# open-lux-C.net
KiCad netlist of a schematic drawn in EAGLE
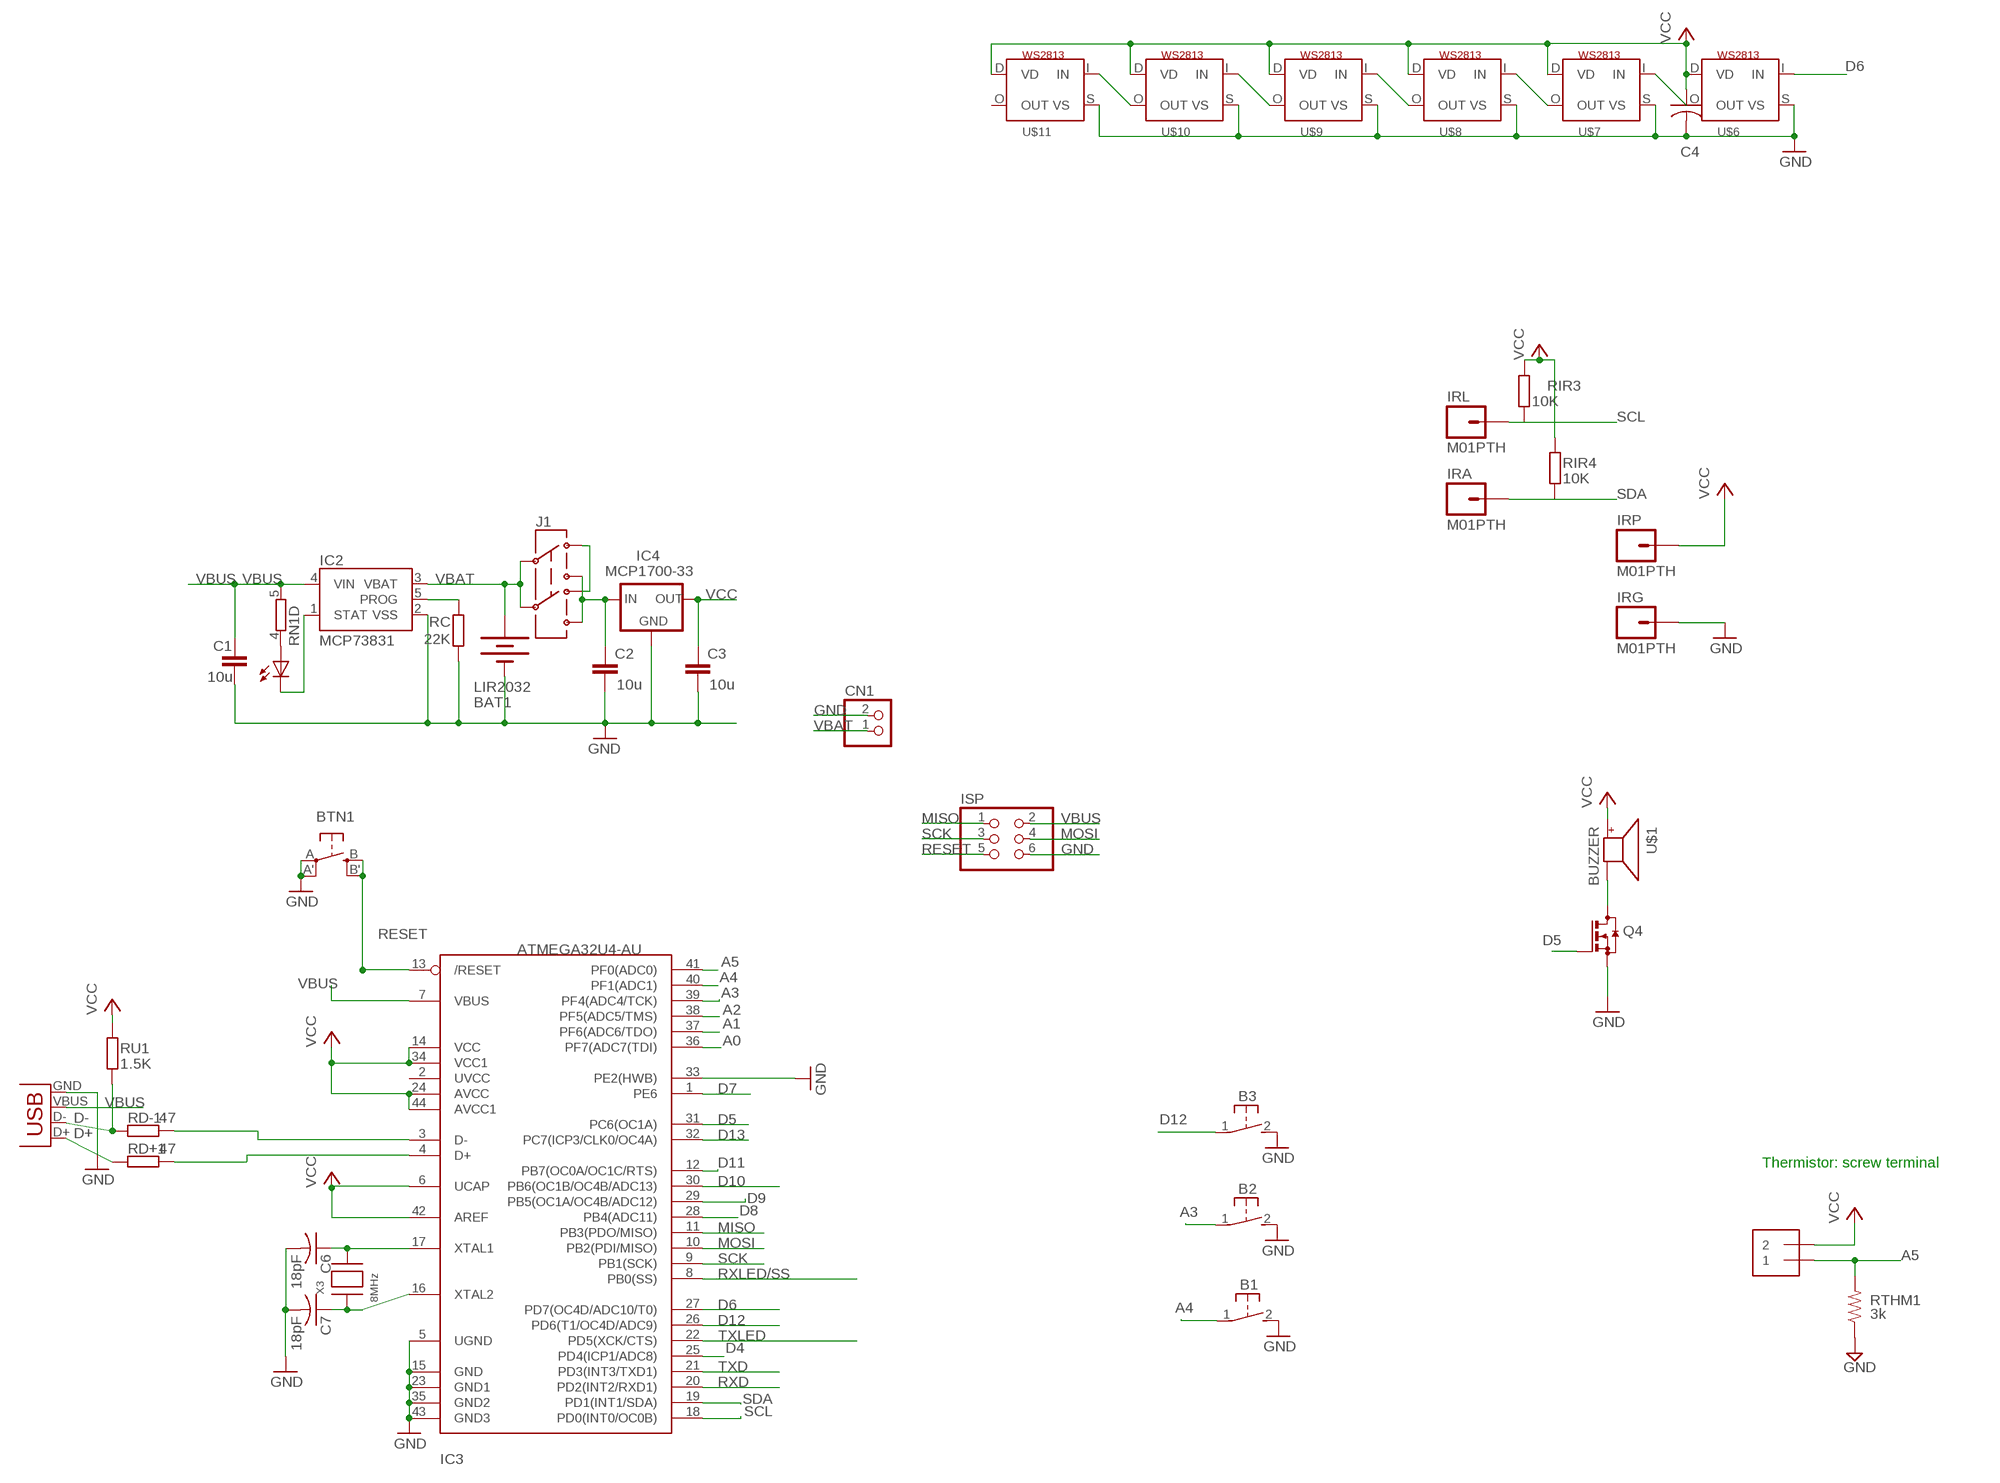
[diagram p0: schematic, sheet 1, part 1 of 2]
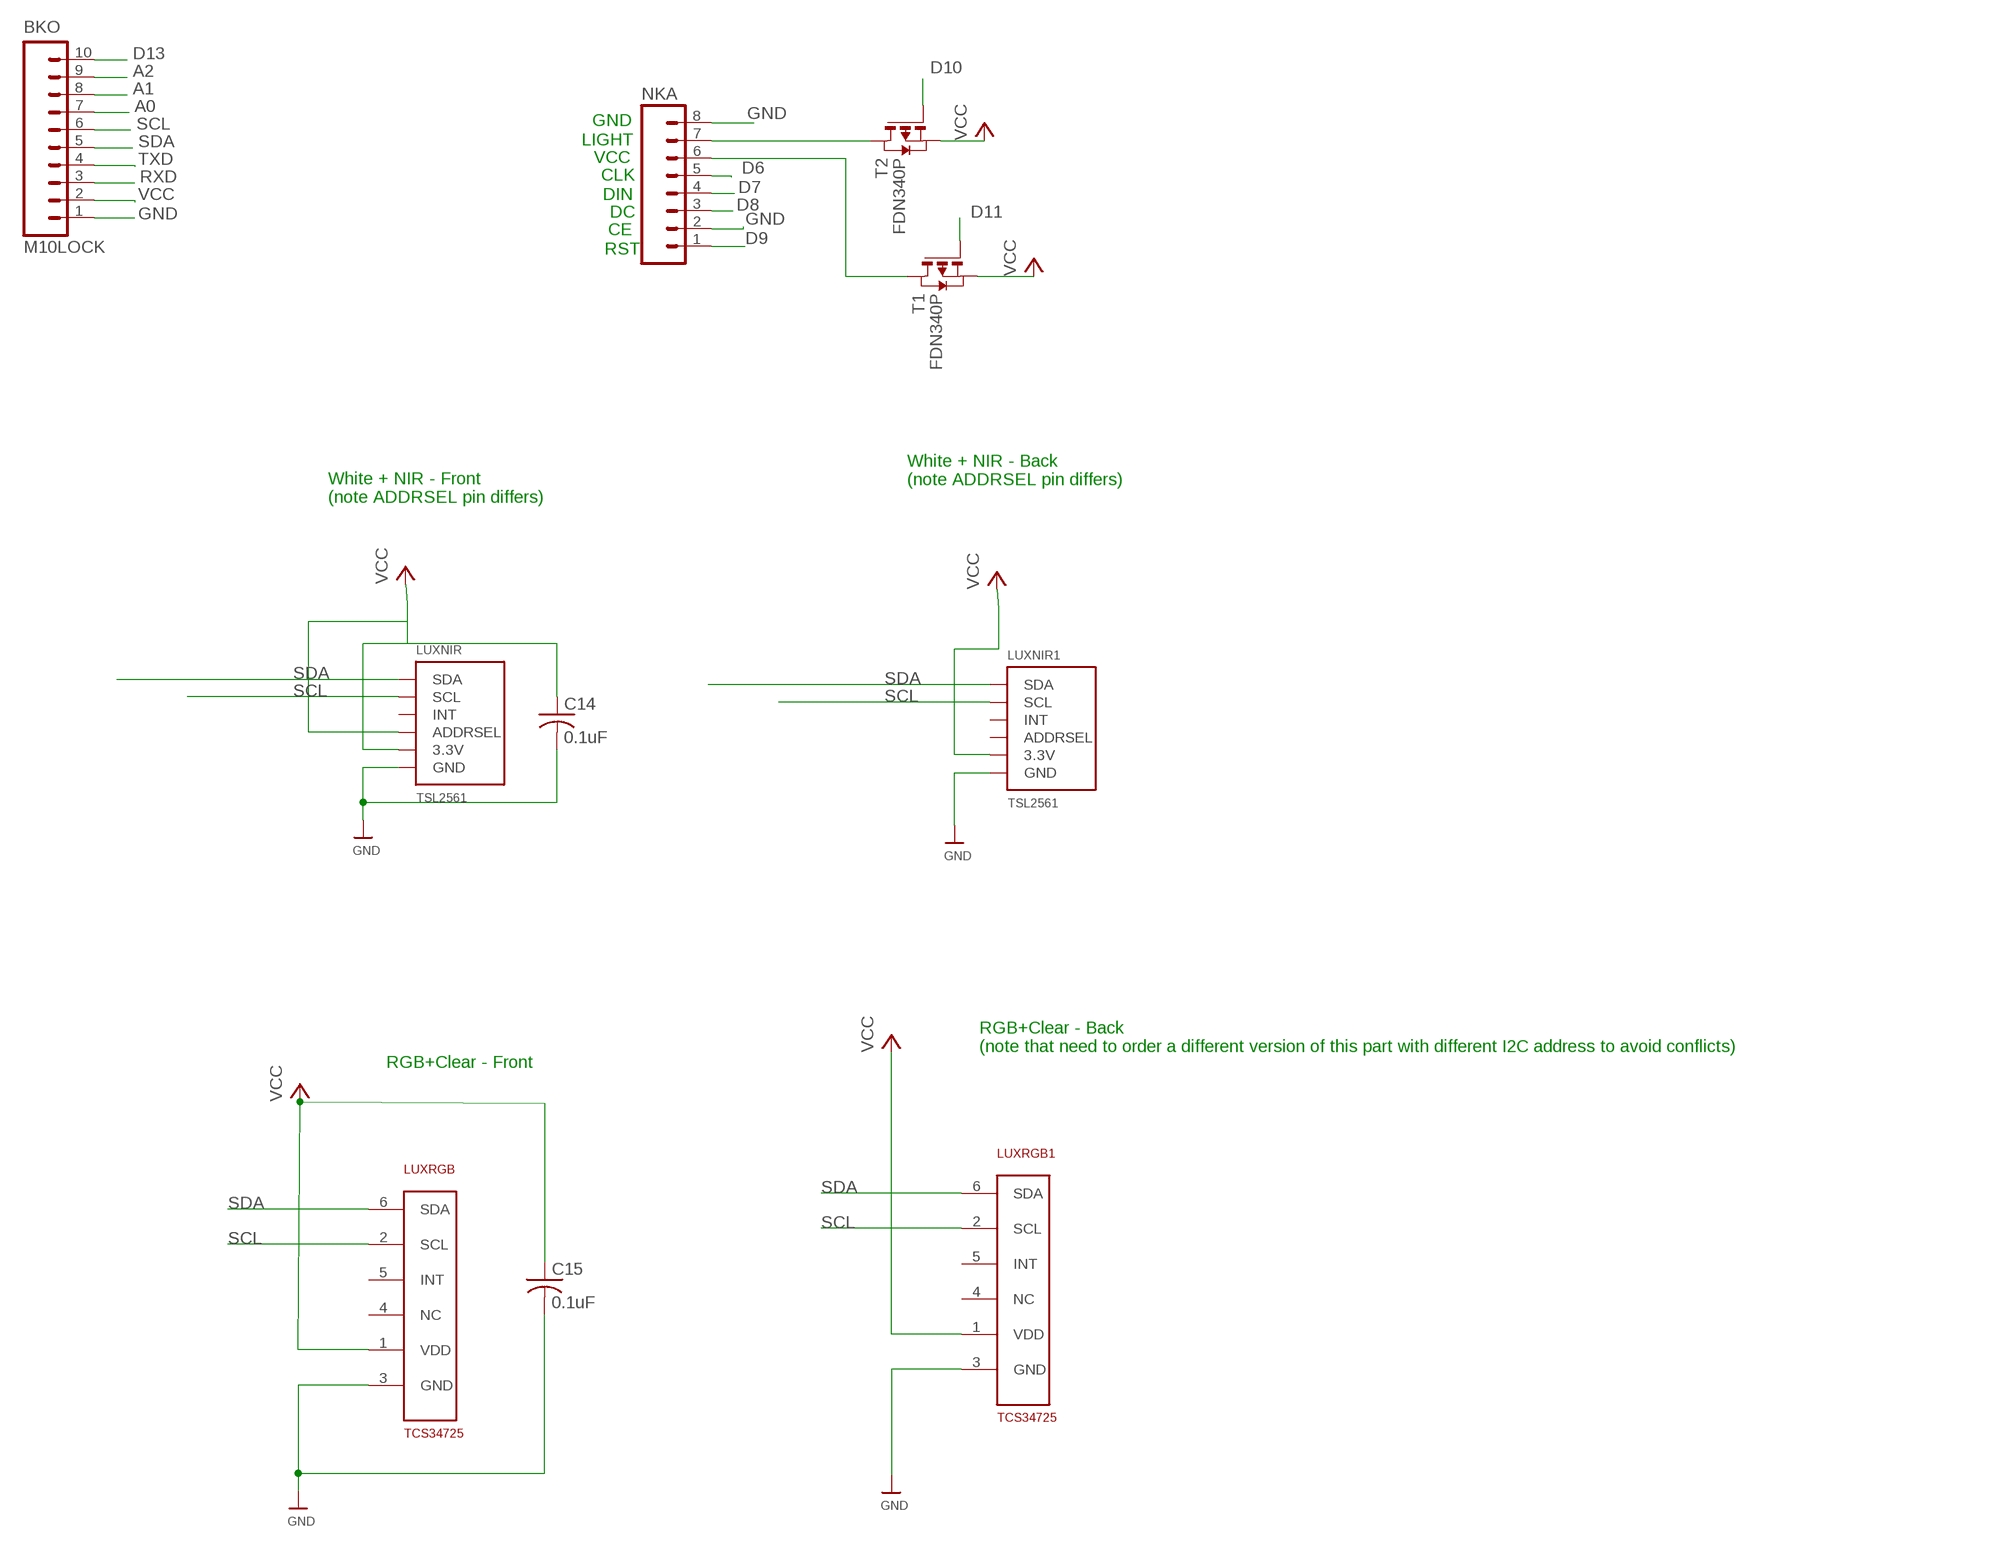
[diagram p1: schematic, sheet 1, part 2 of 2]

(export (version "E")
  (design (tool "Eeschema 10.0.6"))
  (components
    (comp (ref "B1")
      (value "31-XX")
      (footprint "eagle-import:B3F-31XX")
      (libsource (lib "eagle-import") (part "31-XX"))
    )
    (comp (ref "B2")
      (value "31-XX")
      (footprint "eagle-import:B3F-31XX")
      (libsource (lib "eagle-import") (part "31-XX"))
    )
    (comp (ref "B3")
      (value "31-XX")
      (footprint "eagle-import:B3F-31XX")
      (libsource (lib "eagle-import") (part "31-XX"))
    )
    (comp (ref "BAT1")
      (value "LIR2032")
      (footprint "eagle-import:BATTCOM_20MM_PTH_SMT")
      (libsource (lib "eagle-import") (part "BATTERYBATTCOM_20MM_PTH_SMT"))
    )
    (comp (ref "BKO")
      (value "M10LOCK")
      (footprint "eagle-import:1X10_LOCK")
      (libsource (lib "eagle-import") (part "M10LOCK"))
    )
    (comp (ref "BTN1")
      (value "EVQQ2")
      (footprint "eagle-import:EVQ-Q2")
      (libsource (lib "eagle-import") (part "EVQQ2"))
    )
    (comp (ref "C1")
      (value "10u")
      (footprint "eagle-import:C0805")
      (libsource (lib "eagle-import") (part "C-EUC0805"))
    )
    (comp (ref "C2")
      (value "10u")
      (footprint "eagle-import:C0805")
      (libsource (lib "eagle-import") (part "C-EUC0805"))
    )
    (comp (ref "C3")
      (value "10u")
      (footprint "eagle-import:C0805")
      (libsource (lib "eagle-import") (part "C-EUC0805"))
    )
    (comp (ref "C4")
      (value "C-USC0805K")
      (footprint "eagle-import:C0805K")
      (libsource (lib "eagle-import") (part "adafruit2013_C-USC0805K"))
    )
    (comp (ref "C6")
      (value "18pF")
      (footprint "eagle-import:C0805K")
      (libsource (lib "eagle-import") (part "C-USC0805K"))
    )
    (comp (ref "C7")
      (value "18pF")
      (footprint "eagle-import:C0805K")
      (libsource (lib "eagle-import") (part "C-USC0805K"))
    )
    (comp (ref "C14")
      (value "0.1uF")
      (footprint "eagle-import:C0805")
      (libsource (lib "eagle-import") (part "C-USC0805"))
    )
    (comp (ref "C15")
      (value "0.1uF")
      (footprint "eagle-import:C0805")
      (libsource (lib "eagle-import") (part "C-USC0805"))
    )
    (comp (ref "CHG")
      (value "0805")
      (footprint "eagle-import:CHIPLED_0805")
      (libsource (lib "eagle-import") (part "LEDCHIPLED_0805"))
    )
    (comp (ref "CN1")
      (value "JST_2PIN-SMT-RA")
      (footprint "eagle-import:JST-PH-2-SMT-RA")
      (libsource (lib "eagle-import") (part "JST_2PIN-SMT-RA"))
    )
    (comp (ref "IC2")
      (value "MCP73831")
      (footprint "eagle-import:SOT23-5")
      (libsource (lib "eagle-import") (part "MCP73831"))
    )
    (comp (ref "IC3")
      (value "ATMEGA32U4-AU")
      (footprint "eagle-import:TQFP44")
      (libsource (lib "eagle-import") (part "ATMEGA32U4-AU"))
    )
    (comp (ref "IC4")
      (value "MCP1700-33")
      (footprint "eagle-import:SOT23")
      (libsource (lib "eagle-import") (part "MCP1700SOT233"))
    )
    (comp (ref "IRA")
      (value "M01PTH")
      (footprint "eagle-import:1X01")
      (libsource (lib "eagle-import") (part "M01PTH"))
    )
    (comp (ref "IRG")
      (value "M01PTH")
      (footprint "eagle-import:1X01")
      (libsource (lib "eagle-import") (part "M01PTH"))
    )
    (comp (ref "IRL")
      (value "M01PTH")
      (footprint "eagle-import:1X01")
      (libsource (lib "eagle-import") (part "M01PTH"))
    )
    (comp (ref "IRP")
      (value "M01PTH")
      (footprint "eagle-import:1X01")
      (libsource (lib "eagle-import") (part "M01PTH"))
    )
    (comp (ref "ISP")
      (value "PINHD-2X3")
      (footprint "eagle-import:2X03")
      (libsource (lib "eagle-import") (part "PINHD-2X3"))
    )
    (comp (ref "J1")
      (value "AYZ0202")
      (footprint "eagle-import:AYZ0202")
      (libsource (lib "eagle-import") (part "AYZ0202"))
    )
    (comp (ref "LUXNIR")
      (value "TSL2561")
      (footprint "eagle-import:TSL2561_FN@1")
      (libsource (lib "eagle-import") (part "TSL2561"))
    )
    (comp (ref "LUXNIR1")
      (value "TSL2561")
      (footprint "eagle-import:TSL2561_FN@1")
      (libsource (lib "eagle-import") (part "TSL2561"))
    )
    (comp (ref "LUXRGB")
      (value "TCS34725")
      (footprint "eagle-import:DFN-6")
      (libsource (lib "eagle-import") (part "TCS34725"))
    )
    (comp (ref "LUXRGB1")
      (value "TCS34725")
      (footprint "eagle-import:DFN-6")
      (libsource (lib "eagle-import") (part "TCS34725"))
    )
    (comp (ref "NKA")
      (value "M08LOCK")
      (footprint "eagle-import:1X08_LOCK")
      (libsource (lib "eagle-import") (part "M08LOCK"))
    )
    (comp (ref "Q4")
      (value "BSS123")
      (footprint "eagle-import:SOT23")
      (libsource (lib "eagle-import") (part "BSS123"))
    )
    (comp (ref "RC")
      (value "22K")
      (footprint "eagle-import:R0805")
      (libsource (lib "eagle-import") (part "R-EU_R0805"))
    )
    (comp (ref "RD+1")
      (value "47")
      (footprint "eagle-import:R0805")
      (libsource (lib "eagle-import") (part "R-EU_R0805"))
    )
    (comp (ref "RD-1")
      (value "47")
      (footprint "eagle-import:R0805")
      (libsource (lib "eagle-import") (part "R-EU_R0805"))
    )
    (comp (ref "RIR3")
      (value "10K")
      (footprint "eagle-import:R0805")
      (libsource (lib "eagle-import") (part "R-EU_R0805"))
    )
    (comp (ref "RIR4")
      (value "10K")
      (footprint "eagle-import:R0805")
      (libsource (lib "eagle-import") (part "R-EU_R0805"))
    )
    (comp (ref "RN1")
      (value "4R-NEXB38V")
      (footprint "eagle-import:EXB38V")
      (libsource (lib "eagle-import") (part "4R-NEXB38V"))
    )
    (comp (ref "RTHM1")
      (value "3k")
      (footprint "eagle-import:R0805@1")
      (libsource (lib "eagle-import") (part "R-US_R0805"))
    )
    (comp (ref "RU1")
      (value "1.5K")
      (footprint "eagle-import:R0805")
      (libsource (lib "eagle-import") (part "R-EU_R0805"))
    )
    (comp (ref "T1")
      (value "FDN340P")
      (footprint "eagle-import:SOT-23")
      (libsource (lib "eagle-import") (part "PMOSSOT23"))
    )
    (comp (ref "T2")
      (value "FDN340P")
      (footprint "eagle-import:SOT-23")
      (libsource (lib "eagle-import") (part "PMOSSOT23"))
    )
    (comp (ref "THM1")
      (value "1X2-3.5MM")
      (footprint "eagle-import:1X2-3.5MM")
      (libsource (lib "eagle-import") (part "1X2-3.5MM"))
    )
    (comp (ref "U$1")
      (value "BUZZER")
      (footprint "eagle-import:SMT-8585-BUZZER")
      (libsource (lib "eagle-import") (part "BUZZER"))
    )
    (comp (ref "U$6")
      (value "WS2813")
      (footprint "eagle-import:RGBLED5050_4")
      (libsource (lib "eagle-import") (part "WS2813"))
    )
    (comp (ref "U$7")
      (value "WS2813")
      (footprint "eagle-import:RGBLED5050_4")
      (libsource (lib "eagle-import") (part "WS2813"))
    )
    (comp (ref "U$8")
      (value "WS2813")
      (footprint "eagle-import:RGBLED5050_4")
      (libsource (lib "eagle-import") (part "WS2813"))
    )
    (comp (ref "U$9")
      (value "WS2813")
      (footprint "eagle-import:RGBLED5050_4")
      (libsource (lib "eagle-import") (part "WS2813"))
    )
    (comp (ref "U$10")
      (value "WS2813")
      (footprint "eagle-import:RGBLED5050_4")
      (libsource (lib "eagle-import") (part "WS2813"))
    )
    (comp (ref "U$11")
      (value "WS2813")
      (footprint "eagle-import:RGBLED5050_4")
      (libsource (lib "eagle-import") (part "WS2813"))
    )
    (comp (ref "X2")
      (value "USBSMD")
      (footprint "eagle-import:USB-MINIB")
      (libsource (lib "eagle-import") (part "USBSMD"))
    )
    (comp (ref "X3")
      (value "8MHz")
      (footprint "eagle-import:NX5032")
      (libsource (lib "eagle-import") (part "XTALNX5032"))
    )
  )
  (nets
    (net (code "1") (name "/A0") (class "Default")
      (node (ref "BKO") (pin "7") (pinfunction "7_7") (pintype "passive"))
      (node (ref "IC3") (pin "36") (pinfunction "PF7(ADC7(TDI)_36") (pintype "bidirectional"))
    )
    (net (code "2") (name "/A1") (class "Default")
      (node (ref "BKO") (pin "8") (pinfunction "8_8") (pintype "passive"))
      (node (ref "IC3") (pin "37") (pinfunction "PF6(ADC6/TDO)_37") (pintype "bidirectional"))
    )
    (net (code "3") (name "/A2") (class "Default")
      (node (ref "BKO") (pin "9") (pinfunction "9_9") (pintype "passive"))
      (node (ref "IC3") (pin "38") (pinfunction "PF5(ADC5/TMS)_38") (pintype "bidirectional"))
    )
    (net (code "4") (name "/A3") (class "Default")
      (node (ref "B2") (pin "1") (pinfunction "P_1") (pintype "passive"))
      (node (ref "IC3") (pin "39") (pinfunction "PF4(ADC4/TCK)_39") (pintype "bidirectional"))
    )
    (net (code "5") (name "/A4") (class "Default")
      (node (ref "B1") (pin "1") (pinfunction "P_1") (pintype "passive"))
      (node (ref "IC3") (pin "40") (pinfunction "PF1(ADC1)_40") (pintype "bidirectional"))
    )
    (net (code "6") (name "/A5") (class "Default")
      (node (ref "IC3") (pin "41") (pinfunction "PF0(ADC0)_41") (pintype "bidirectional"))
      (node (ref "RTHM1") (pin "2") (pinfunction "2_2") (pintype "passive"))
      (node (ref "THM1") (pin "1") (pinfunction "1_1") (pintype "passive"))
    )
    (net (code "7") (name "/D+") (class "Default")
      (node (ref "RD+1") (pin "1") (pinfunction "1_1") (pintype "passive"))
      (node (ref "X2") (pin "D+") (pinfunction "D+_D+") (pintype "bidirectional"))
    )
    (net (code "8") (name "/D-") (class "Default")
      (node (ref "RD-1") (pin "1") (pinfunction "1_1") (pintype "passive"))
      (node (ref "RU1") (pin "1") (pinfunction "1_1") (pintype "passive"))
      (node (ref "X2") (pin "D-") (pinfunction "D-_D-") (pintype "bidirectional"))
    )
    (net (code "9") (name "/D4") (class "Default")
      (node (ref "IC3") (pin "25") (pinfunction "PD4(ICP1/ADC8)_25") (pintype "bidirectional"))
    )
    (net (code "10") (name "/D5") (class "Default")
      (node (ref "IC3") (pin "31") (pinfunction "PC6(OC1A)_31") (pintype "bidirectional"))
      (node (ref "Q4") (pin "1") (pinfunction "G_1") (pintype "passive"))
    )
    (net (code "11") (name "/D6") (class "Default")
      (node (ref "IC3") (pin "27") (pinfunction "PD7(OC4D/ADC10/T0)_27") (pintype "bidirectional"))
      (node (ref "NKA") (pin "5") (pinfunction "5_5") (pintype "passive"))
      (node (ref "U$6") (pin "I") (pinfunction "IN_I") (pintype "input"))
    )
    (net (code "12") (name "/D7") (class "Default")
      (node (ref "IC3") (pin "1") (pinfunction "PE6_1") (pintype "bidirectional"))
      (node (ref "NKA") (pin "4") (pinfunction "4_4") (pintype "passive"))
    )
    (net (code "13") (name "/D8") (class "Default")
      (node (ref "IC3") (pin "28") (pinfunction "PB4(ADC11)_28") (pintype "bidirectional"))
      (node (ref "NKA") (pin "3") (pinfunction "3_3") (pintype "passive"))
    )
    (net (code "14") (name "/D9") (class "Default")
      (node (ref "IC3") (pin "29") (pinfunction "PB5(OC1A/OC4B/ADC12)_29") (pintype "bidirectional"))
      (node (ref "NKA") (pin "1") (pinfunction "1_1") (pintype "passive"))
    )
    (net (code "15") (name "/D10") (class "Default")
      (node (ref "IC3") (pin "30") (pinfunction "PB6(OC1B/OC4B/ADC13)_30") (pintype "bidirectional"))
      (node (ref "T2") (pin "3") (pinfunction "G_3") (pintype "passive"))
    )
    (net (code "16") (name "/D11") (class "Default")
      (node (ref "IC3") (pin "12") (pinfunction "PB7(OC0A/OC1C/RTS)_12") (pintype "bidirectional"))
      (node (ref "T1") (pin "3") (pinfunction "G_3") (pintype "passive"))
    )
    (net (code "17") (name "/D12") (class "Default")
      (node (ref "B3") (pin "1") (pinfunction "P_1") (pintype "passive"))
      (node (ref "IC3") (pin "26") (pinfunction "PD6(T1/OC4D/ADC9)_26") (pintype "bidirectional"))
    )
    (net (code "18") (name "/D13") (class "Default")
      (node (ref "BKO") (pin "10") (pinfunction "10_10") (pintype "passive"))
      (node (ref "IC3") (pin "32") (pinfunction "PC7(ICP3/CLK0/OC4A)_32") (pintype "bidirectional"))
    )
    (net (code "19") (name "/MISO") (class "Default")
      (node (ref "IC3") (pin "11") (pinfunction "PB3(PDO/MISO)_11") (pintype "bidirectional"))
      (node (ref "ISP") (pin "1") (pinfunction "1_1") (pintype "passive"))
    )
    (net (code "20") (name "/MOSI") (class "Default")
      (node (ref "IC3") (pin "10") (pinfunction "PB2(PDI/MISO)_10") (pintype "bidirectional"))
      (node (ref "ISP") (pin "4") (pinfunction "4_4") (pintype "passive"))
    )
    (net (code "21") (name "/RESET") (class "Default")
      (node (ref "BTN1") (pin "B") (pinfunction "S_B") (pintype "passive"))
      (node (ref "BTN1") (pin "B'") (pinfunction "S1_B'") (pintype "passive"))
      (node (ref "IC3") (pin "13") (pinfunction "/RESET_13") (pintype "bidirectional"))
      (node (ref "ISP") (pin "5") (pinfunction "5_5") (pintype "passive"))
    )
    (net (code "22") (name "/RXD") (class "Default")
      (node (ref "BKO") (pin "3") (pinfunction "3_3") (pintype "passive"))
      (node (ref "IC3") (pin "20") (pinfunction "PD2(INT2/RXD1)_20") (pintype "bidirectional"))
    )
    (net (code "23") (name "/RXLED{slash}SS") (class "Default")
      (node (ref "IC3") (pin "8") (pinfunction "PB0(SS)_8") (pintype "bidirectional"))
    )
    (net (code "24") (name "/SCK") (class "Default")
      (node (ref "IC3") (pin "9") (pinfunction "PB1(SCK)_9") (pintype "bidirectional"))
      (node (ref "ISP") (pin "3") (pinfunction "3_3") (pintype "passive"))
    )
    (net (code "25") (name "/SCL") (class "Default")
      (node (ref "BKO") (pin "6") (pinfunction "6_6") (pintype "passive"))
      (node (ref "IC3") (pin "18") (pinfunction "PD0(INT0/OC0B)_18") (pintype "bidirectional"))
      (node (ref "IRL") (pin "1") (pinfunction "1_1") (pintype "passive"))
      (node (ref "LUXNIR") (pin "CLK") (pinfunction "SCL_CLK") (pintype "bidirectional"))
      (node (ref "LUXNIR1") (pin "CLK") (pinfunction "SCL_CLK") (pintype "bidirectional"))
      (node (ref "LUXRGB") (pin "2") (pinfunction "SCL_2") (pintype "bidirectional"))
      (node (ref "LUXRGB1") (pin "2") (pinfunction "SCL_2") (pintype "bidirectional"))
      (node (ref "RIR3") (pin "1") (pinfunction "1_1") (pintype "passive"))
    )
    (net (code "26") (name "/SDA") (class "Default")
      (node (ref "BKO") (pin "5") (pinfunction "5_5") (pintype "passive"))
      (node (ref "IC3") (pin "19") (pinfunction "PD1(INT1/SDA)_19") (pintype "bidirectional"))
      (node (ref "IRA") (pin "1") (pinfunction "1_1") (pintype "passive"))
      (node (ref "LUXNIR") (pin "DATA") (pinfunction "SDA_DATA") (pintype "bidirectional"))
      (node (ref "LUXNIR1") (pin "DATA") (pinfunction "SDA_DATA") (pintype "bidirectional"))
      (node (ref "LUXRGB") (pin "6") (pinfunction "SDA_6") (pintype "bidirectional"))
      (node (ref "LUXRGB1") (pin "6") (pinfunction "SDA_6") (pintype "bidirectional"))
      (node (ref "RIR4") (pin "1") (pinfunction "1_1") (pintype "passive"))
    )
    (net (code "27") (name "/TXD") (class "Default")
      (node (ref "BKO") (pin "4") (pinfunction "4_4") (pintype "passive"))
      (node (ref "IC3") (pin "21") (pinfunction "PD3(INT3/TXD1)_21") (pintype "bidirectional"))
    )
    (net (code "28") (name "/TXLED") (class "Default")
      (node (ref "IC3") (pin "22") (pinfunction "PD5(XCK/CTS)_22") (pintype "bidirectional"))
    )
    (net (code "29") (name "/VBAT") (class "Default")
      (node (ref "BAT1") (pin "P$2") (pinfunction "+_P$2") (pintype "power_in"))
      (node (ref "CN1") (pin "1") (pinfunction "2_1") (pintype "passive"))
      (node (ref "IC2") (pin "3") (pinfunction "VBAT_3") (pintype "power_in"))
      (node (ref "J1") (pin "2") (pinfunction "2_2") (pintype "bidirectional"))
      (node (ref "J1") (pin "5") (pinfunction "5_5") (pintype "bidirectional"))
    )
    (net (code "30") (name "/VBUS") (class "Default")
      (node (ref "C1") (pin "1") (pinfunction "1_1") (pintype "passive"))
      (node (ref "IC2") (pin "4") (pinfunction "VIN_4") (pintype "power_in"))
      (node (ref "IC3") (pin "7") (pinfunction "VBUS_7") (pintype "bidirectional"))
      (node (ref "ISP") (pin "2") (pinfunction "2_2") (pintype "passive"))
      (node (ref "RN1") (pin "5") (pinfunction "2_5") (pintype "passive"))
      (node (ref "X2") (pin "VBUS") (pinfunction "VBUS_VBUS") (pintype "bidirectional"))
    )
    (net (code "31") (name "GND") (class "Default")
      (node (ref "B1") (pin "2") (pinfunction "S_2") (pintype "passive"))
      (node (ref "B2") (pin "2") (pinfunction "S_2") (pintype "passive"))
      (node (ref "B3") (pin "2") (pinfunction "S_2") (pintype "passive"))
      (node (ref "BAT1") (pin "P$1") (pinfunction "-_P$1") (pintype "power_in"))
      (node (ref "BKO") (pin "1") (pinfunction "1_1") (pintype "passive"))
      (node (ref "BTN1") (pin "A") (pinfunction "P_A") (pintype "passive"))
      (node (ref "BTN1") (pin "A'") (pinfunction "P1_A'") (pintype "passive"))
      (node (ref "C1") (pin "2") (pinfunction "2_2") (pintype "passive"))
      (node (ref "C14") (pin "2") (pinfunction "2_2") (pintype "passive"))
      (node (ref "C15") (pin "2") (pinfunction "2_2") (pintype "passive"))
      (node (ref "C2") (pin "2") (pinfunction "2_2") (pintype "passive"))
      (node (ref "C3") (pin "2") (pinfunction "2_2") (pintype "passive"))
      (node (ref "C4") (pin "2") (pinfunction "2_2") (pintype "passive"))
      (node (ref "C6") (pin "2") (pinfunction "2_2") (pintype "passive"))
      (node (ref "C7") (pin "2") (pinfunction "2_2") (pintype "passive"))
      (node (ref "CN1") (pin "2") (pinfunction "1_2") (pintype "passive"))
      (node (ref "IC2") (pin "2") (pinfunction "VSS_2") (pintype "power_in"))
      (node (ref "IC3") (pin "15") (pinfunction "GND_15") (pintype "bidirectional"))
      (node (ref "IC3") (pin "23") (pinfunction "GND1_23") (pintype "bidirectional"))
      (node (ref "IC3") (pin "33") (pinfunction "PE2(HWB)_33") (pintype "bidirectional"))
      (node (ref "IC3") (pin "35") (pinfunction "GND2_35") (pintype "bidirectional"))
      (node (ref "IC3") (pin "43") (pinfunction "GND3_43") (pintype "bidirectional"))
      (node (ref "IC3") (pin "5") (pinfunction "UGND_5") (pintype "bidirectional"))
      (node (ref "IC4") (pin "1") (pinfunction "GND_1") (pintype "input"))
      (node (ref "IRG") (pin "1") (pinfunction "1_1") (pintype "passive"))
      (node (ref "ISP") (pin "6") (pinfunction "6_6") (pintype "passive"))
      (node (ref "LUXNIR") (pin "VSS") (pinfunction "GND_VSS") (pintype "bidirectional"))
      (node (ref "LUXNIR1") (pin "VSS") (pinfunction "GND_VSS") (pintype "bidirectional"))
      (node (ref "LUXRGB") (pin "3") (pinfunction "GND_3") (pintype "bidirectional"))
      (node (ref "LUXRGB1") (pin "3") (pinfunction "GND_3") (pintype "bidirectional"))
      (node (ref "NKA") (pin "2") (pinfunction "2_2") (pintype "passive"))
      (node (ref "NKA") (pin "8") (pinfunction "8_8") (pintype "passive"))
      (node (ref "Q4") (pin "2") (pinfunction "S_2") (pintype "passive"))
      (node (ref "RC") (pin "1") (pinfunction "1_1") (pintype "passive"))
      (node (ref "RTHM1") (pin "1") (pinfunction "1_1") (pintype "passive"))
      (node (ref "U$10") (pin "S") (pinfunction "VS_S") (pintype "power_in"))
      (node (ref "U$11") (pin "S") (pinfunction "VS_S") (pintype "power_in"))
      (node (ref "U$6") (pin "S") (pinfunction "VS_S") (pintype "power_in"))
      (node (ref "U$7") (pin "S") (pinfunction "VS_S") (pintype "power_in"))
      (node (ref "U$8") (pin "S") (pinfunction "VS_S") (pintype "power_in"))
      (node (ref "U$9") (pin "S") (pinfunction "VS_S") (pintype "power_in"))
      (node (ref "X2") (pin "GND") (pinfunction "GND_GND") (pintype "bidirectional"))
    )
    (net (code "32") (name "Net-(IC2-PROG)") (class "Default")
      (node (ref "IC2") (pin "5") (pinfunction "PROG_5") (pintype "input"))
      (node (ref "RC") (pin "2") (pinfunction "2_2") (pintype "passive"))
    )
    (net (code "33") (name "Net-(IC2-STAT)") (class "Default")
      (node (ref "CHG") (pin "C") (pinfunction "C_C") (pintype "passive"))
      (node (ref "IC2") (pin "1") (pinfunction "STAT_1") (pintype "output"))
    )
    (net (code "34") (name "Net-(IC3-D+)") (class "Default")
      (node (ref "IC3") (pin "4") (pinfunction "D+_4") (pintype "bidirectional"))
      (node (ref "RD+1") (pin "2") (pinfunction "2_2") (pintype "passive"))
    )
    (net (code "35") (name "Net-(IC3-D-)") (class "Default")
      (node (ref "IC3") (pin "3") (pinfunction "D-_3") (pintype "bidirectional"))
      (node (ref "RD-1") (pin "2") (pinfunction "2_2") (pintype "passive"))
    )
    (net (code "36") (name "Net-(IC3-XTAL1)") (class "Default")
      (node (ref "C6") (pin "1") (pinfunction "1_1") (pintype "passive"))
      (node (ref "IC3") (pin "17") (pinfunction "XTAL1_17") (pintype "bidirectional"))
      (node (ref "X3") (pin "P$2") (pinfunction "P$2_P$2") (pintype "bidirectional"))
    )
    (net (code "37") (name "Net-(IC3-XTAL2)") (class "Default")
      (node (ref "C7") (pin "1") (pinfunction "1_1") (pintype "passive"))
      (node (ref "IC3") (pin "16") (pinfunction "XTAL2_16") (pintype "bidirectional"))
      (node (ref "X3") (pin "P$1") (pinfunction "P$1_P$1") (pintype "bidirectional"))
    )
    (net (code "38") (name "Net-(IC4-IN)") (class "Default")
      (node (ref "C2") (pin "1") (pinfunction "1_1") (pintype "passive"))
      (node (ref "IC4") (pin "3") (pinfunction "IN_3") (pintype "input"))
      (node (ref "J1") (pin "1") (pinfunction "3_1") (pintype "bidirectional"))
      (node (ref "J1") (pin "4") (pinfunction "6_4") (pintype "bidirectional"))
    )
    (net (code "39") (name "Net-(J1-1)") (class "Default")
      (node (ref "J1") (pin "3") (pinfunction "1_3") (pintype "bidirectional"))
      (node (ref "J1") (pin "6") (pinfunction "4_6") (pintype "bidirectional"))
    )
    (net (code "40") (name "Net-(Q4-D)") (class "Default")
      (node (ref "Q4") (pin "3") (pinfunction "D_3") (pintype "passive"))
      (node (ref "U$1") (pin "-") (pinfunction "-_-") (pintype "passive"))
    )
    (net (code "41") (name "Net-(RN1D-1)") (class "Default")
      (node (ref "CHG") (pin "A") (pinfunction "A_A") (pintype "passive"))
      (node (ref "RN1") (pin "4") (pinfunction "1_4") (pintype "passive"))
    )
    (net (code "42") (name "Net-(T1-D)") (class "Default")
      (node (ref "NKA") (pin "6") (pinfunction "6_6") (pintype "passive"))
      (node (ref "T1") (pin "1") (pinfunction "D_1") (pintype "passive"))
    )
    (net (code "43") (name "Net-(T2-D)") (class "Default")
      (node (ref "NKA") (pin "7") (pinfunction "7_7") (pintype "passive"))
      (node (ref "T2") (pin "1") (pinfunction "D_1") (pintype "passive"))
    )
    (net (code "44") (name "Net-(U$6-OUT)") (class "Default")
      (node (ref "U$6") (pin "O") (pinfunction "OUT_O") (pintype "output"))
      (node (ref "U$7") (pin "I") (pinfunction "IN_I") (pintype "input"))
    )
    (net (code "45") (name "Net-(U$7-OUT)") (class "Default")
      (node (ref "U$7") (pin "O") (pinfunction "OUT_O") (pintype "output"))
      (node (ref "U$8") (pin "I") (pinfunction "IN_I") (pintype "input"))
    )
    (net (code "46") (name "Net-(U$8-OUT)") (class "Default")
      (node (ref "U$8") (pin "O") (pinfunction "OUT_O") (pintype "output"))
      (node (ref "U$9") (pin "I") (pinfunction "IN_I") (pintype "input"))
    )
    (net (code "47") (name "Net-(U$10-IN)") (class "Default")
      (node (ref "U$10") (pin "I") (pinfunction "IN_I") (pintype "input"))
      (node (ref "U$9") (pin "O") (pinfunction "OUT_O") (pintype "output"))
    )
    (net (code "48") (name "Net-(U$10-OUT)") (class "Default")
      (node (ref "U$10") (pin "O") (pinfunction "OUT_O") (pintype "output"))
      (node (ref "U$11") (pin "I") (pinfunction "IN_I") (pintype "input"))
    )
    (net (code "49") (name "VCC") (class "Default")
      (node (ref "BKO") (pin "2") (pinfunction "2_2") (pintype "passive"))
      (node (ref "C14") (pin "1") (pinfunction "1_1") (pintype "passive"))
      (node (ref "C15") (pin "1") (pinfunction "1_1") (pintype "passive"))
      (node (ref "C3") (pin "1") (pinfunction "1_1") (pintype "passive"))
      (node (ref "C4") (pin "1") (pinfunction "1_1") (pintype "passive"))
      (node (ref "IC3") (pin "14") (pinfunction "VCC_14") (pintype "bidirectional"))
      (node (ref "IC3") (pin "24") (pinfunction "AVCC_24") (pintype "bidirectional"))
      (node (ref "IC3") (pin "34") (pinfunction "VCC1_34") (pintype "bidirectional"))
      (node (ref "IC3") (pin "42") (pinfunction "AREF_42") (pintype "bidirectional"))
      (node (ref "IC3") (pin "44") (pinfunction "AVCC1_44") (pintype "bidirectional"))
      (node (ref "IC3") (pin "6") (pinfunction "UCAP_6") (pintype "bidirectional"))
      (node (ref "IC4") (pin "2") (pinfunction "OUT_2") (pintype "passive"))
      (node (ref "IRP") (pin "1") (pinfunction "1_1") (pintype "passive"))
      (node (ref "LUXNIR") (pin "ADR") (pinfunction "ADDRSEL_ADR") (pintype "bidirectional"))
      (node (ref "LUXNIR") (pin "VDD") (pinfunction "3.3V_VDD") (pintype "bidirectional"))
      (node (ref "LUXNIR1") (pin "VDD") (pinfunction "3.3V_VDD") (pintype "bidirectional"))
      (node (ref "LUXRGB") (pin "1") (pinfunction "VDD_1") (pintype "bidirectional"))
      (node (ref "LUXRGB1") (pin "1") (pinfunction "VDD_1") (pintype "bidirectional"))
      (node (ref "RIR3") (pin "2") (pinfunction "2_2") (pintype "passive"))
      (node (ref "RIR4") (pin "2") (pinfunction "2_2") (pintype "passive"))
      (node (ref "RU1") (pin "2") (pinfunction "2_2") (pintype "passive"))
      (node (ref "T1") (pin "2") (pinfunction "S_2") (pintype "passive"))
      (node (ref "T2") (pin "2") (pinfunction "S_2") (pintype "passive"))
      (node (ref "THM1") (pin "2") (pinfunction "2_2") (pintype "passive"))
      (node (ref "U$1") (pin "+") (pinfunction "+_+") (pintype "passive"))
      (node (ref "U$10") (pin "D") (pinfunction "VD_D") (pintype "power_in"))
      (node (ref "U$11") (pin "D") (pinfunction "VD_D") (pintype "power_in"))
      (node (ref "U$6") (pin "D") (pinfunction "VD_D") (pintype "power_in"))
      (node (ref "U$7") (pin "D") (pinfunction "VD_D") (pintype "power_in"))
      (node (ref "U$8") (pin "D") (pinfunction "VD_D") (pintype "power_in"))
      (node (ref "U$9") (pin "D") (pinfunction "VD_D") (pintype "power_in"))
    )
    (net (code "50") (name "unconnected-(IC3-UVCC-Pad2)") (class "Default")
      (node (ref "IC3") (pin "2") (pinfunction "UVCC_2") (pintype "bidirectional"))
    )
    (net (code "51") (name "unconnected-(LUXNIR-PadINT)") (class "Default")
      (node (ref "LUXNIR") (pin "INT") (pinfunction "INT_INT") (pintype "bidirectional"))
    )
    (net (code "52") (name "unconnected-(LUXNIR1-ADDRSEL-PadADR)") (class "Default")
      (node (ref "LUXNIR1") (pin "ADR") (pinfunction "ADDRSEL_ADR") (pintype "bidirectional"))
    )
    (net (code "53") (name "unconnected-(LUXNIR1-PadINT)") (class "Default")
      (node (ref "LUXNIR1") (pin "INT") (pinfunction "INT_INT") (pintype "bidirectional"))
    )
    (net (code "54") (name "unconnected-(LUXRGB-INT-Pad5)") (class "Default")
      (node (ref "LUXRGB") (pin "5") (pinfunction "INT_5") (pintype "bidirectional"))
    )
    (net (code "55") (name "unconnected-(LUXRGB-NC-Pad4)") (class "Default")
      (node (ref "LUXRGB") (pin "4") (pinfunction "NC_4") (pintype "bidirectional"))
    )
    (net (code "56") (name "unconnected-(LUXRGB1-INT-Pad5)") (class "Default")
      (node (ref "LUXRGB1") (pin "5") (pinfunction "INT_5") (pintype "bidirectional"))
    )
    (net (code "57") (name "unconnected-(LUXRGB1-NC-Pad4)") (class "Default")
      (node (ref "LUXRGB1") (pin "4") (pinfunction "NC_4") (pintype "bidirectional"))
    )
    (net (code "58") (name "unconnected-(U$11-OUT-PadO)") (class "Default")
      (node (ref "U$11") (pin "O") (pinfunction "OUT_O") (pintype "output"))
    )
  )
)
